# untitled.net
KiCad netlist of a schematic drawn in EAGLE
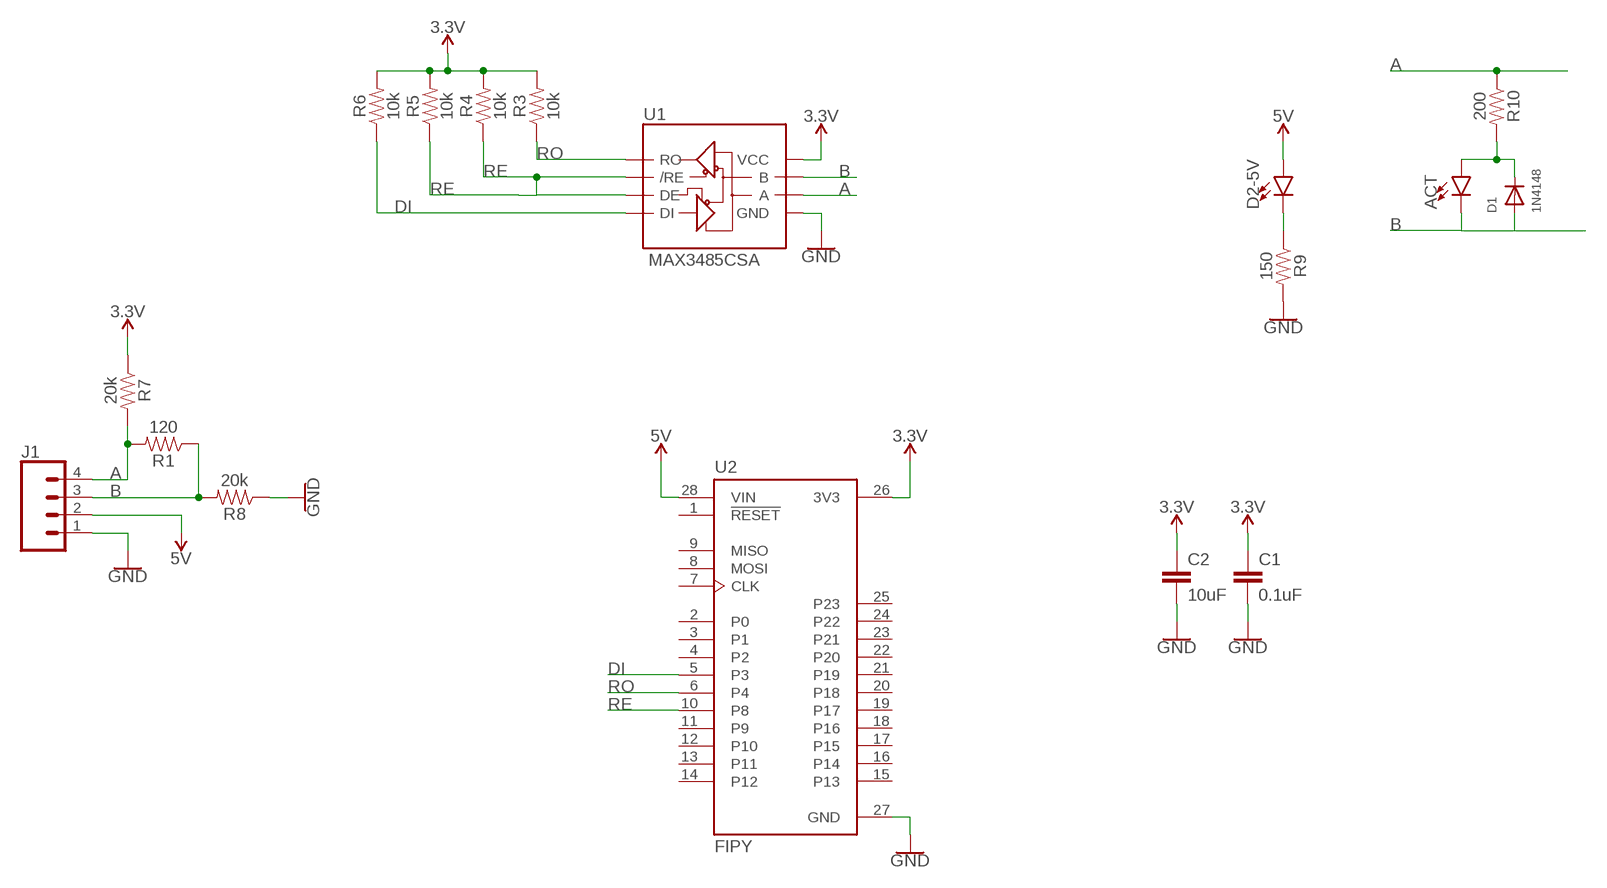
[diagram p0: schematic, sheet 1]

(export (version "E")
  (design (tool "Eeschema 10.0.6"))
  (components
    (comp (ref "ACT")
      (value "LED0603")
      (footprint "eagle-import:LED-0603")
      (libsource (lib "eagle-import") (part "LED0603"))
    )
    (comp (ref "C1")
      (value "0.1uF")
      (footprint "eagle-import:0603")
      (libsource (lib "eagle-import") (part "0.1UF-0603-25V-5%"))
    )
    (comp (ref "C2")
      (value "10uF")
      (footprint "eagle-import:0603")
      (libsource (lib "eagle-import") (part "10UF-0603-6.3V-20%"))
    )
    (comp (ref "D1")
      (value "1N4148")
      (footprint "eagle-import:SOD-123")
      (libsource (lib "eagle-import") (part "DIODESOD-123"))
    )
    (comp (ref "D2-5V")
      (value "LED0603")
      (footprint "eagle-import:LED-0603")
      (libsource (lib "eagle-import") (part "LED0603"))
    )
    (comp (ref "J1")
      (value "CONN_04LOCK_LONGPADS")
      (footprint "eagle-import:1X04_LOCK_LONGPADS")
      (libsource (lib "eagle-import") (part "CONN_04LOCK_LONGPADS"))
    )
    (comp (ref "R1")
      (value "120")
      (footprint "eagle-import:0805")
      (libsource (lib "eagle-import") (part "0.3OHM-0805-1/8W-1%"))
    )
    (comp (ref "R3")
      (value "10k")
      (footprint "eagle-import:0603")
      (libsource (lib "eagle-import") (part "10KOHM-0603-1/10W-1%"))
    )
    (comp (ref "R4")
      (value "10k")
      (footprint "eagle-import:0603")
      (libsource (lib "eagle-import") (part "10KOHM-0603-1/10W-1%"))
    )
    (comp (ref "R5")
      (value "10k")
      (footprint "eagle-import:0603")
      (libsource (lib "eagle-import") (part "10KOHM-0603-1/10W-1%"))
    )
    (comp (ref "R6")
      (value "10k")
      (footprint "eagle-import:0603")
      (libsource (lib "eagle-import") (part "10KOHM-0603-1/10W-1%"))
    )
    (comp (ref "R7")
      (value "20k")
      (footprint "eagle-import:0805")
      (libsource (lib "eagle-import") (part "0.3OHM-0805-1/8W-1%"))
    )
    (comp (ref "R8")
      (value "20k")
      (footprint "eagle-import:0805")
      (libsource (lib "eagle-import") (part "0.3OHM-0805-1/8W-1%"))
    )
    (comp (ref "R9")
      (value "150")
      (footprint "eagle-import:0805")
      (libsource (lib "eagle-import") (part "0.3OHM-0805-1/8W-1%"))
    )
    (comp (ref "R10")
      (value "200")
      (footprint "eagle-import:0805")
      (libsource (lib "eagle-import") (part "0.3OHM-0805-1/8W-1%"))
    )
    (comp (ref "U1")
      (value "MAX3485CSA")
      (footprint "eagle-import:SO08")
      (libsource (lib "eagle-import") (part "RS485SOIC"))
    )
    (comp (ref "U2")
      (value "FIPY")
      (footprint "eagle-import:MODULE_FIPY")
      (fields (field (name "MF") "Pycom Ltd."))
      (libsource (lib "eagle-import") (part "FIPY"))
    )
  )
  (nets
    (net (code "1") (name "/A") (class "Default")
      (node (ref "J1") (pin "4") (pinfunction "4_4") (pintype "passive"))
      (node (ref "R1") (pin "2") (pinfunction "2_2") (pintype "passive"))
      (node (ref "R10") (pin "1") (pinfunction "1_1") (pintype "passive"))
      (node (ref "R7") (pin "2") (pinfunction "2_2") (pintype "passive"))
      (node (ref "U1") (pin "6") (pinfunction "A_6") (pintype "bidirectional"))
    )
    (net (code "2") (name "/B") (class "Default")
      (node (ref "ACT") (pin "C") (pinfunction "C_C") (pintype "passive"))
      (node (ref "D1") (pin "A") (pinfunction "A_A") (pintype "passive"))
      (node (ref "J1") (pin "3") (pinfunction "3_3") (pintype "passive"))
      (node (ref "R1") (pin "1") (pinfunction "1_1") (pintype "passive"))
      (node (ref "R8") (pin "2") (pinfunction "2_2") (pintype "passive"))
      (node (ref "U1") (pin "7") (pinfunction "B_7") (pintype "bidirectional"))
    )
    (net (code "3") (name "/DI") (class "Default")
      (node (ref "R6") (pin "1") (pinfunction "1_1") (pintype "passive"))
      (node (ref "U1") (pin "4") (pinfunction "DI_4") (pintype "bidirectional"))
      (node (ref "U2") (pin "5") (pinfunction "P3_5") (pintype "bidirectional"))
    )
    (net (code "4") (name "/RE") (class "Default")
      (node (ref "R4") (pin "1") (pinfunction "1_1") (pintype "passive"))
      (node (ref "R5") (pin "1") (pinfunction "1_1") (pintype "passive"))
      (node (ref "U1") (pin "2") (pinfunction "/RE_2") (pintype "bidirectional"))
      (node (ref "U1") (pin "3") (pinfunction "DE_3") (pintype "bidirectional"))
      (node (ref "U2") (pin "10") (pinfunction "P8_10") (pintype "bidirectional"))
    )
    (net (code "5") (name "/RO") (class "Default")
      (node (ref "R3") (pin "1") (pinfunction "1_1") (pintype "passive"))
      (node (ref "U1") (pin "1") (pinfunction "RO_1") (pintype "bidirectional"))
      (node (ref "U2") (pin "6") (pinfunction "P4_6") (pintype "bidirectional"))
    )
    (net (code "6") (name "3.3V") (class "Default")
      (node (ref "C1") (pin "1") (pinfunction "1_1") (pintype "passive"))
      (node (ref "C2") (pin "1") (pinfunction "1_1") (pintype "passive"))
      (node (ref "R3") (pin "2") (pinfunction "2_2") (pintype "passive"))
      (node (ref "R4") (pin "2") (pinfunction "2_2") (pintype "passive"))
      (node (ref "R5") (pin "2") (pinfunction "2_2") (pintype "passive"))
      (node (ref "R6") (pin "2") (pinfunction "2_2") (pintype "passive"))
      (node (ref "R7") (pin "1") (pinfunction "1_1") (pintype "passive"))
      (node (ref "U1") (pin "8") (pinfunction "VCC_8") (pintype "bidirectional"))
      (node (ref "U2") (pin "26") (pinfunction "3V3_26") (pintype "output"))
    )
    (net (code "7") (name "5V") (class "Default")
      (node (ref "D2-5V") (pin "A") (pinfunction "A_A") (pintype "passive"))
      (node (ref "J1") (pin "2") (pinfunction "2_2") (pintype "passive"))
      (node (ref "U2") (pin "28") (pinfunction "VIN_28") (pintype "input"))
    )
    (net (code "8") (name "GND") (class "Default")
      (node (ref "C1") (pin "2") (pinfunction "2_2") (pintype "passive"))
      (node (ref "C2") (pin "2") (pinfunction "2_2") (pintype "passive"))
      (node (ref "J1") (pin "1") (pinfunction "1_1") (pintype "passive"))
      (node (ref "R8") (pin "1") (pinfunction "1_1") (pintype "passive"))
      (node (ref "R9") (pin "2") (pinfunction "2_2") (pintype "passive"))
      (node (ref "U1") (pin "5") (pinfunction "GND_5") (pintype "bidirectional"))
      (node (ref "U2") (pin "27") (pinfunction "GND_27") (pintype "power_in"))
    )
    (net (code "9") (name "Net-(ACT-PadA)") (class "Default")
      (node (ref "ACT") (pin "A") (pinfunction "A_A") (pintype "passive"))
      (node (ref "D1") (pin "C") (pinfunction "C_C") (pintype "passive"))
      (node (ref "R10") (pin "2") (pinfunction "2_2") (pintype "passive"))
    )
    (net (code "10") (name "Net-(D2-5V-PadC)") (class "Default")
      (node (ref "D2-5V") (pin "C") (pinfunction "C_C") (pintype "passive"))
      (node (ref "R9") (pin "1") (pinfunction "1_1") (pintype "passive"))
    )
    (net (code "11") (name "unconnected-(U2-CLK-Pad7)") (class "Default")
      (node (ref "U2") (pin "7") (pinfunction "CLK_7") (pintype "input"))
    )
    (net (code "12") (name "unconnected-(U2-MISO-Pad9)") (class "Default")
      (node (ref "U2") (pin "9") (pinfunction "MISO_9") (pintype "output"))
    )
    (net (code "13") (name "unconnected-(U2-MOSI-Pad8)") (class "Default")
      (node (ref "U2") (pin "8") (pinfunction "MOSI_8") (pintype "input"))
    )
    (net (code "14") (name "unconnected-(U2-P0-Pad2)") (class "Default")
      (node (ref "U2") (pin "2") (pinfunction "P0_2") (pintype "bidirectional"))
    )
    (net (code "15") (name "unconnected-(U2-P1-Pad3)") (class "Default")
      (node (ref "U2") (pin "3") (pinfunction "P1_3") (pintype "bidirectional"))
    )
    (net (code "16") (name "unconnected-(U2-P2-Pad4)") (class "Default")
      (node (ref "U2") (pin "4") (pinfunction "P2_4") (pintype "bidirectional"))
    )
    (net (code "17") (name "unconnected-(U2-P9-Pad11)") (class "Default")
      (node (ref "U2") (pin "11") (pinfunction "P9_11") (pintype "bidirectional"))
    )
    (net (code "18") (name "unconnected-(U2-P10-Pad12)") (class "Default")
      (node (ref "U2") (pin "12") (pinfunction "P10_12") (pintype "bidirectional"))
    )
    (net (code "19") (name "unconnected-(U2-P11-Pad13)") (class "Default")
      (node (ref "U2") (pin "13") (pinfunction "P11_13") (pintype "bidirectional"))
    )
    (net (code "20") (name "unconnected-(U2-P12-Pad14)") (class "Default")
      (node (ref "U2") (pin "14") (pinfunction "P12_14") (pintype "bidirectional"))
    )
    (net (code "21") (name "unconnected-(U2-P13-Pad15)") (class "Default")
      (node (ref "U2") (pin "15") (pinfunction "P13_15") (pintype "input"))
    )
    (net (code "22") (name "unconnected-(U2-P14-Pad16)") (class "Default")
      (node (ref "U2") (pin "16") (pinfunction "P14_16") (pintype "input"))
    )
    (net (code "23") (name "unconnected-(U2-P15-Pad17)") (class "Default")
      (node (ref "U2") (pin "17") (pinfunction "P15_17") (pintype "input"))
    )
    (net (code "24") (name "unconnected-(U2-P16-Pad18)") (class "Default")
      (node (ref "U2") (pin "18") (pinfunction "P16_18") (pintype "input"))
    )
    (net (code "25") (name "unconnected-(U2-P17-Pad19)") (class "Default")
      (node (ref "U2") (pin "19") (pinfunction "P17_19") (pintype "input"))
    )
    (net (code "26") (name "unconnected-(U2-P18-Pad20)") (class "Default")
      (node (ref "U2") (pin "20") (pinfunction "P18_20") (pintype "input"))
    )
    (net (code "27") (name "unconnected-(U2-P19-Pad21)") (class "Default")
      (node (ref "U2") (pin "21") (pinfunction "P19_21") (pintype "bidirectional"))
    )
    (net (code "28") (name "unconnected-(U2-P20-Pad22)") (class "Default")
      (node (ref "U2") (pin "22") (pinfunction "P20_22") (pintype "bidirectional"))
    )
    (net (code "29") (name "unconnected-(U2-P21-Pad23)") (class "Default")
      (node (ref "U2") (pin "23") (pinfunction "P21_23") (pintype "bidirectional"))
    )
    (net (code "30") (name "unconnected-(U2-P22-Pad24)") (class "Default")
      (node (ref "U2") (pin "24") (pinfunction "P22_24") (pintype "bidirectional"))
    )
    (net (code "31") (name "unconnected-(U2-P23-Pad25)") (class "Default")
      (node (ref "U2") (pin "25") (pinfunction "P23_25") (pintype "bidirectional"))
    )
    (net (code "32") (name "unconnected-(U2-~{RESET}-Pad1)") (class "Default")
      (node (ref "U2") (pin "1") (pinfunction "~{RESET}_1") (pintype "input"))
    )
  )
)
